# clocky.net
KiCad netlist of a schematic drawn in EAGLE
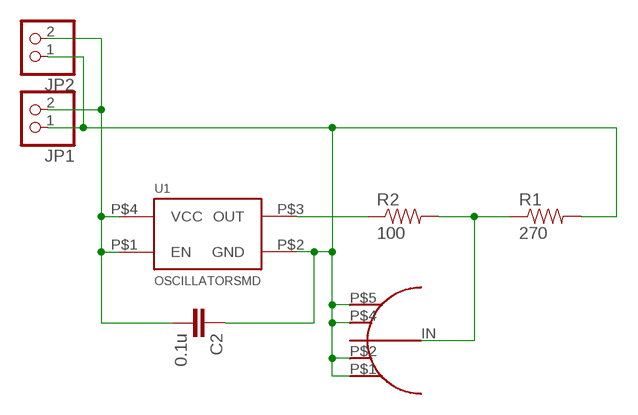
[diagram p0: schematic, sheet 1]

(export (version "E")
  (design (tool "Eeschema 10.0.6"))
  (components
    (comp (ref "C2")
      (value "0.1u")
      (footprint "eagle-import:0603-CAP")
      (libsource (lib "eagle-import") (part "CAP0603-CAP"))
    )
    (comp (ref "JP1")
      (value "PINHD-1X2/90")
      (footprint "eagle-import:1X02_90")
      (libsource (lib "eagle-import") (part "PINHD-1X2/90"))
    )
    (comp (ref "JP2")
      (value "PINHD-1X2")
      (footprint "eagle-import:1X02")
      (libsource (lib "eagle-import") (part "PINHD-1X2"))
    )
    (comp (ref "R1")
      (value "270")
      (footprint "eagle-import:0603-RES")
      (libsource (lib "eagle-import") (part "RESISTOR0603-RES"))
    )
    (comp (ref "R2")
      (value "100")
      (footprint "eagle-import:0603-RES")
      (libsource (lib "eagle-import") (part "RESISTOR0603-RES"))
    )
    (comp (ref "U$1")
      (value "J658")
      (footprint "eagle-import:SMA_J658")
      (libsource (lib "eagle-import") (part "J658"))
    )
    (comp (ref "U1")
      (value "OSCILLATORSMD")
      (footprint "eagle-import:CRYSTAL-SMD-7X5")
      (libsource (lib "eagle-import") (part "OSCILLATORSMD"))
    )
  )
  (nets
    (net (code "1") (name "Net-(R1-Pad1)") (class "Default")
      (node (ref "R1") (pin "1") (pinfunction "1_1") (pintype "passive"))
      (node (ref "R2") (pin "2") (pinfunction "2_2") (pintype "passive"))
      (node (ref "U$1") (pin "IN") (pinfunction "IN_IN") (pintype "bidirectional"))
    )
    (net (code "2") (name "Net-(U$1-GNDA)") (class "Default")
      (node (ref "C2") (pin "1") (pinfunction "1_1") (pintype "passive"))
      (node (ref "JP1") (pin "1") (pinfunction "1_1") (pintype "passive"))
      (node (ref "JP2") (pin "1") (pinfunction "1_1") (pintype "passive"))
      (node (ref "R1") (pin "2") (pinfunction "2_2") (pintype "passive"))
      (node (ref "U$1") (pin "P$1") (pinfunction "GNDA_P$1") (pintype "bidirectional"))
      (node (ref "U$1") (pin "P$2") (pinfunction "GNDB_P$2") (pintype "bidirectional"))
      (node (ref "U$1") (pin "P$4") (pinfunction "GNDC_P$4") (pintype "bidirectional"))
      (node (ref "U$1") (pin "P$5") (pinfunction "GNDD_P$5") (pintype "bidirectional"))
      (node (ref "U1") (pin "P$2") (pinfunction "GND_P$2") (pintype "bidirectional"))
    )
    (net (code "3") (name "Net-(U1-EN)") (class "Default")
      (node (ref "C2") (pin "2") (pinfunction "2_2") (pintype "passive"))
      (node (ref "JP1") (pin "2") (pinfunction "2_2") (pintype "passive"))
      (node (ref "JP2") (pin "2") (pinfunction "2_2") (pintype "passive"))
      (node (ref "U1") (pin "P$1") (pinfunction "EN_P$1") (pintype "bidirectional"))
      (node (ref "U1") (pin "P$4") (pinfunction "VCC_P$4") (pintype "bidirectional"))
    )
    (net (code "4") (name "Net-(U1-OUT)") (class "Default")
      (node (ref "R2") (pin "1") (pinfunction "1_1") (pintype "passive"))
      (node (ref "U1") (pin "P$3") (pinfunction "OUT_P$3") (pintype "bidirectional"))
    )
  )
)
